# GabozePocaio-Extension-Aux.net
KiCad netlist of a schematic drawn in EAGLE
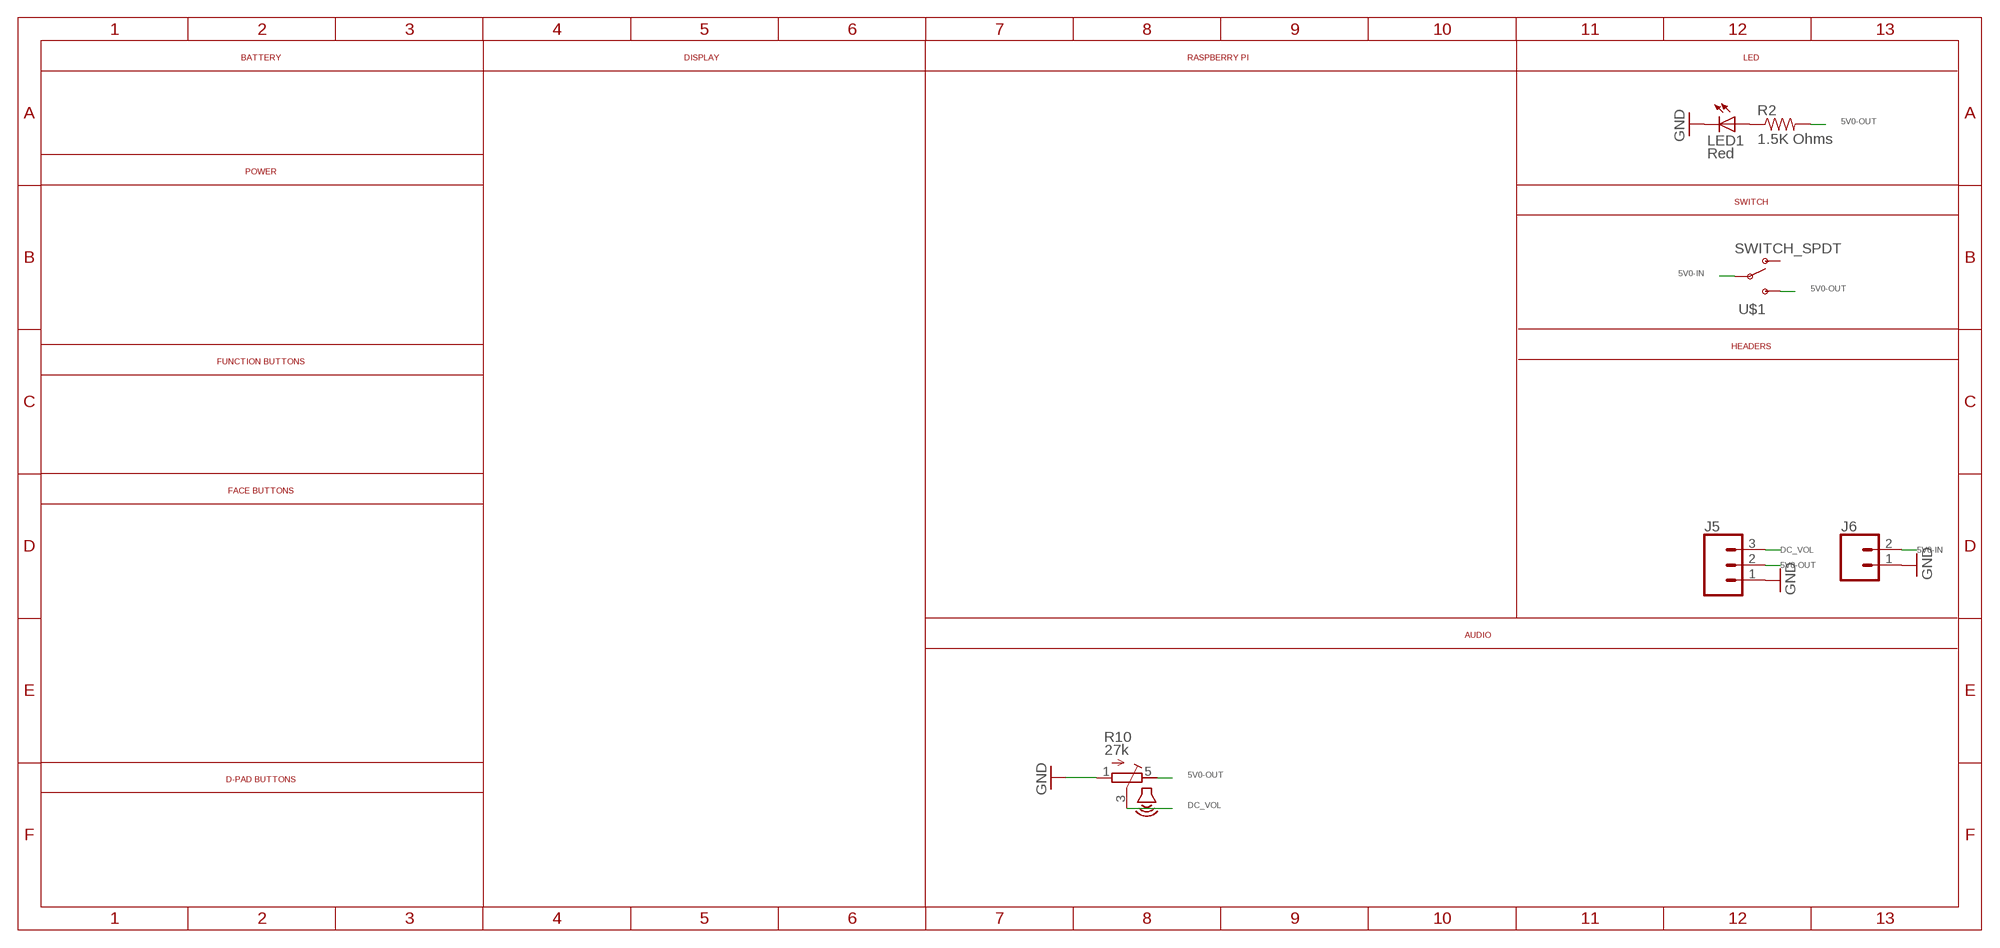
[diagram p0: schematic, sheet 1]

(export (version "E")
  (design (tool "Eeschema 10.0.6"))
  (components
    (comp (ref "J5")
      (value "CONN_031X03_NO_SILK")
      (footprint "eagle-import:1X03_NO_SILK")
      (libsource (lib "eagle-import") (part "CONN_031X03_NO_SILK"))
    )
    (comp (ref "J6")
      (value "CONN_021X02_NO_SILK")
      (footprint "eagle-import:1X02_NO_SILK")
      (libsource (lib "eagle-import") (part "CONN_021X02_NO_SILK"))
    )
    (comp (ref "LED1")
      (value "Red")
      (footprint "eagle-import:LED3MM")
      (libsource (lib "eagle-import") (part "LED3MM"))
    )
    (comp (ref "R2")
      (value "1.5K Ohms")
      (footprint "eagle-import:R0805")
      (libsource (lib "eagle-import") (part "R-US_R0805"))
    )
    (comp (ref "R10")
      (value "27k")
      (footprint "eagle-import:VOLUME")
      (libsource (lib "eagle-import") (part "VOLUME"))
    )
    (comp (ref "U$1")
      (value "SWITCH_SPDT")
      (footprint "eagle-import:KPS-1290")
      (libsource (lib "eagle-import") (part "SWITCH_SPDT"))
    )
  )
  (nets
    (net (code "1") (name "/5V0-IN") (class "Default")
      (node (ref "J6") (pin "2") (pinfunction "2_2") (pintype "passive"))
      (node (ref "U$1") (pin "P") (pinfunction "P_P") (pintype "passive"))
    )
    (net (code "2") (name "/5V0-OUT") (class "Default")
      (node (ref "J5") (pin "2") (pinfunction "2_2") (pintype "passive"))
      (node (ref "R10") (pin "5") (pinfunction "E_5") (pintype "passive"))
      (node (ref "R2") (pin "2") (pinfunction "2_2") (pintype "passive"))
      (node (ref "U$1") (pin "S") (pinfunction "S_S") (pintype "passive"))
    )
    (net (code "3") (name "/DC_VOL") (class "Default")
      (node (ref "J5") (pin "3") (pinfunction "3_3") (pintype "passive"))
      (node (ref "R10") (pin "3") (pinfunction "S_3") (pintype "passive"))
    )
    (net (code "4") (name "GND") (class "Default")
      (node (ref "J5") (pin "1") (pinfunction "1_1") (pintype "passive"))
      (node (ref "J6") (pin "1") (pinfunction "1_1") (pintype "passive"))
      (node (ref "LED1") (pin "K") (pinfunction "C_K") (pintype "passive"))
      (node (ref "R10") (pin "1") (pinfunction "A_1") (pintype "passive"))
    )
    (net (code "5") (name "Net-(LED1-PadA)") (class "Default")
      (node (ref "LED1") (pin "A") (pinfunction "A_A") (pintype "passive"))
      (node (ref "R2") (pin "1") (pinfunction "1_1") (pintype "passive"))
    )
    (net (code "6") (name "unconnected-(U$1-PadO)") (class "Default")
      (node (ref "U$1") (pin "O") (pinfunction "O_O") (pintype "passive"))
    )
  )
)
